# RJ45_connector_y.net
KiCad netlist of a schematic drawn in EAGLE
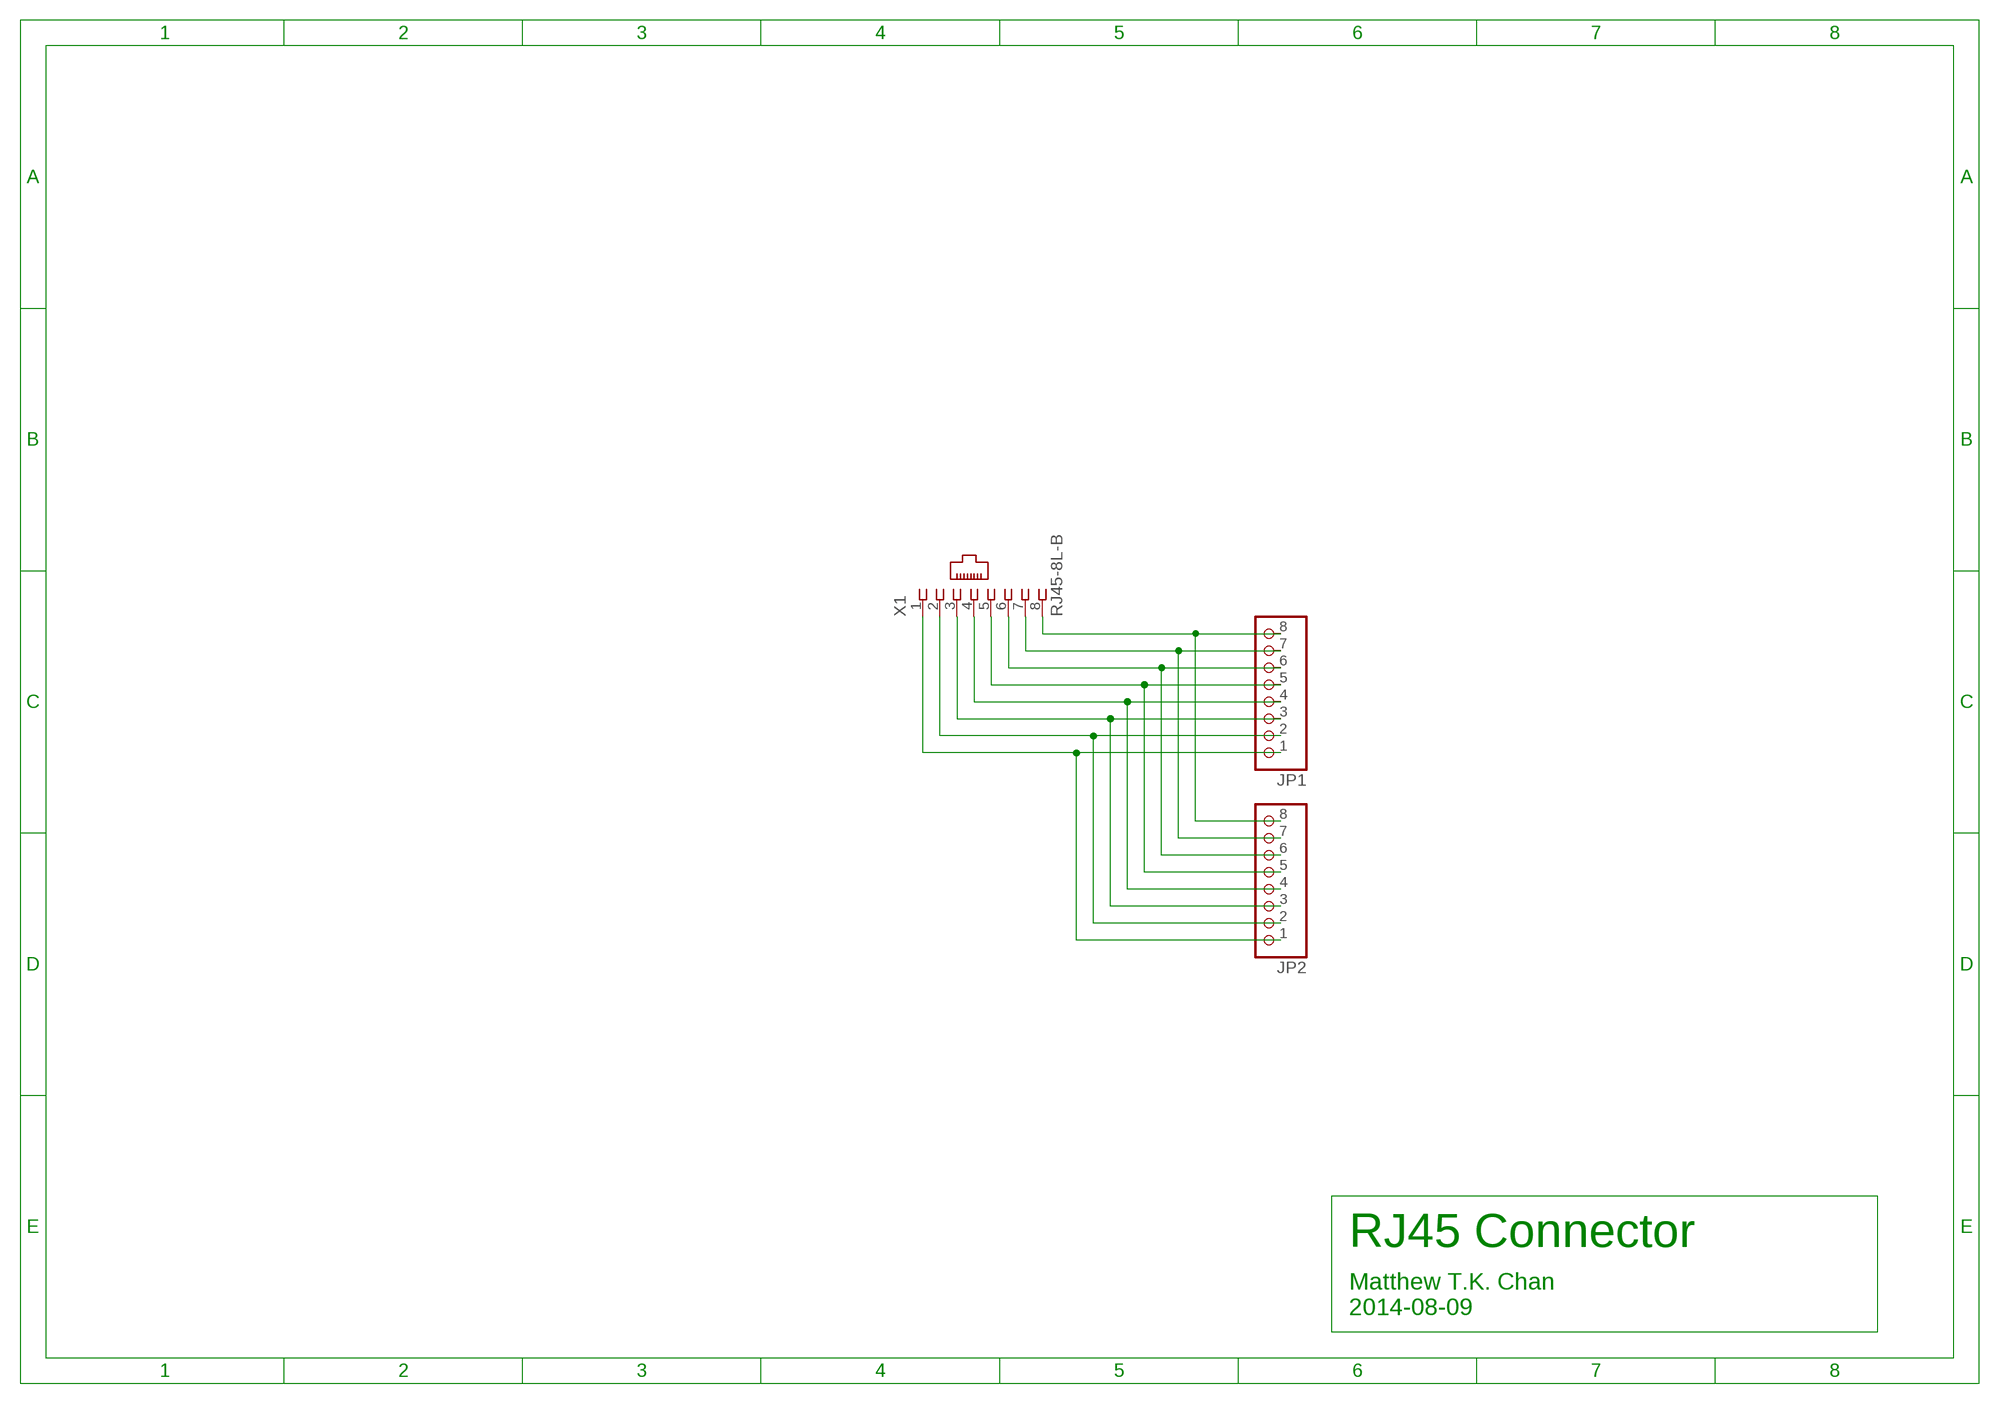
[diagram p0: schematic, sheet 1]

(export (version "E")
  (design (tool "Eeschema 10.0.6"))
  (components
    (comp (ref "JP1")
      (value "PINHD-1X8")
      (footprint "eagle-import:1X08")
      (libsource (lib "eagle-import") (part "PINHD-1X8"))
    )
    (comp (ref "JP2")
      (value "PINHD-1X8")
      (footprint "eagle-import:1X08")
      (libsource (lib "eagle-import") (part "PINHD-1X8"))
    )
    (comp (ref "X1")
      (value "RJ45-8L-B")
      (footprint "eagle-import:RJ45-NO-SHIELD")
      (fields (field (name "MF") "TYCO ELECTRONICS"))
      (libsource (lib "eagle-import") (part "RJ45-8L-B"))
    )
  )
  (nets
    (net (code "1") (name "Net-(JP1-Pad1)") (class "Default")
      (node (ref "JP1") (pin "1") (pinfunction "1_1") (pintype "passive"))
      (node (ref "JP2") (pin "1") (pinfunction "1_1") (pintype "passive"))
      (node (ref "X1") (pin "1") (pinfunction "1_1") (pintype "passive"))
    )
    (net (code "2") (name "Net-(JP1-Pad2)") (class "Default")
      (node (ref "JP1") (pin "2") (pinfunction "2_2") (pintype "passive"))
      (node (ref "JP2") (pin "2") (pinfunction "2_2") (pintype "passive"))
      (node (ref "X1") (pin "2") (pinfunction "2_2") (pintype "passive"))
    )
    (net (code "3") (name "Net-(JP1-Pad3)") (class "Default")
      (node (ref "JP1") (pin "3") (pinfunction "3_3") (pintype "passive"))
      (node (ref "JP2") (pin "3") (pinfunction "3_3") (pintype "passive"))
      (node (ref "X1") (pin "3") (pinfunction "3_3") (pintype "passive"))
    )
    (net (code "4") (name "Net-(JP1-Pad4)") (class "Default")
      (node (ref "JP1") (pin "4") (pinfunction "4_4") (pintype "passive"))
      (node (ref "JP2") (pin "4") (pinfunction "4_4") (pintype "passive"))
      (node (ref "X1") (pin "4") (pinfunction "4_4") (pintype "passive"))
    )
    (net (code "5") (name "Net-(JP1-Pad5)") (class "Default")
      (node (ref "JP1") (pin "5") (pinfunction "5_5") (pintype "passive"))
      (node (ref "JP2") (pin "5") (pinfunction "5_5") (pintype "passive"))
      (node (ref "X1") (pin "5") (pinfunction "5_5") (pintype "passive"))
    )
    (net (code "6") (name "Net-(JP1-Pad6)") (class "Default")
      (node (ref "JP1") (pin "6") (pinfunction "6_6") (pintype "passive"))
      (node (ref "JP2") (pin "6") (pinfunction "6_6") (pintype "passive"))
      (node (ref "X1") (pin "6") (pinfunction "6_6") (pintype "passive"))
    )
    (net (code "7") (name "Net-(JP1-Pad7)") (class "Default")
      (node (ref "JP1") (pin "7") (pinfunction "7_7") (pintype "passive"))
      (node (ref "JP2") (pin "7") (pinfunction "7_7") (pintype "passive"))
      (node (ref "X1") (pin "7") (pinfunction "7_7") (pintype "passive"))
    )
    (net (code "8") (name "Net-(JP1-Pad8)") (class "Default")
      (node (ref "JP1") (pin "8") (pinfunction "8_8") (pintype "passive"))
      (node (ref "JP2") (pin "8") (pinfunction "8_8") (pintype "passive"))
      (node (ref "X1") (pin "8") (pinfunction "8_8") (pintype "passive"))
    )
  )
)
